# FEV-60_Motor_Driver_Mcu.net
KiCad netlist of a schematic drawn in Altium Designer
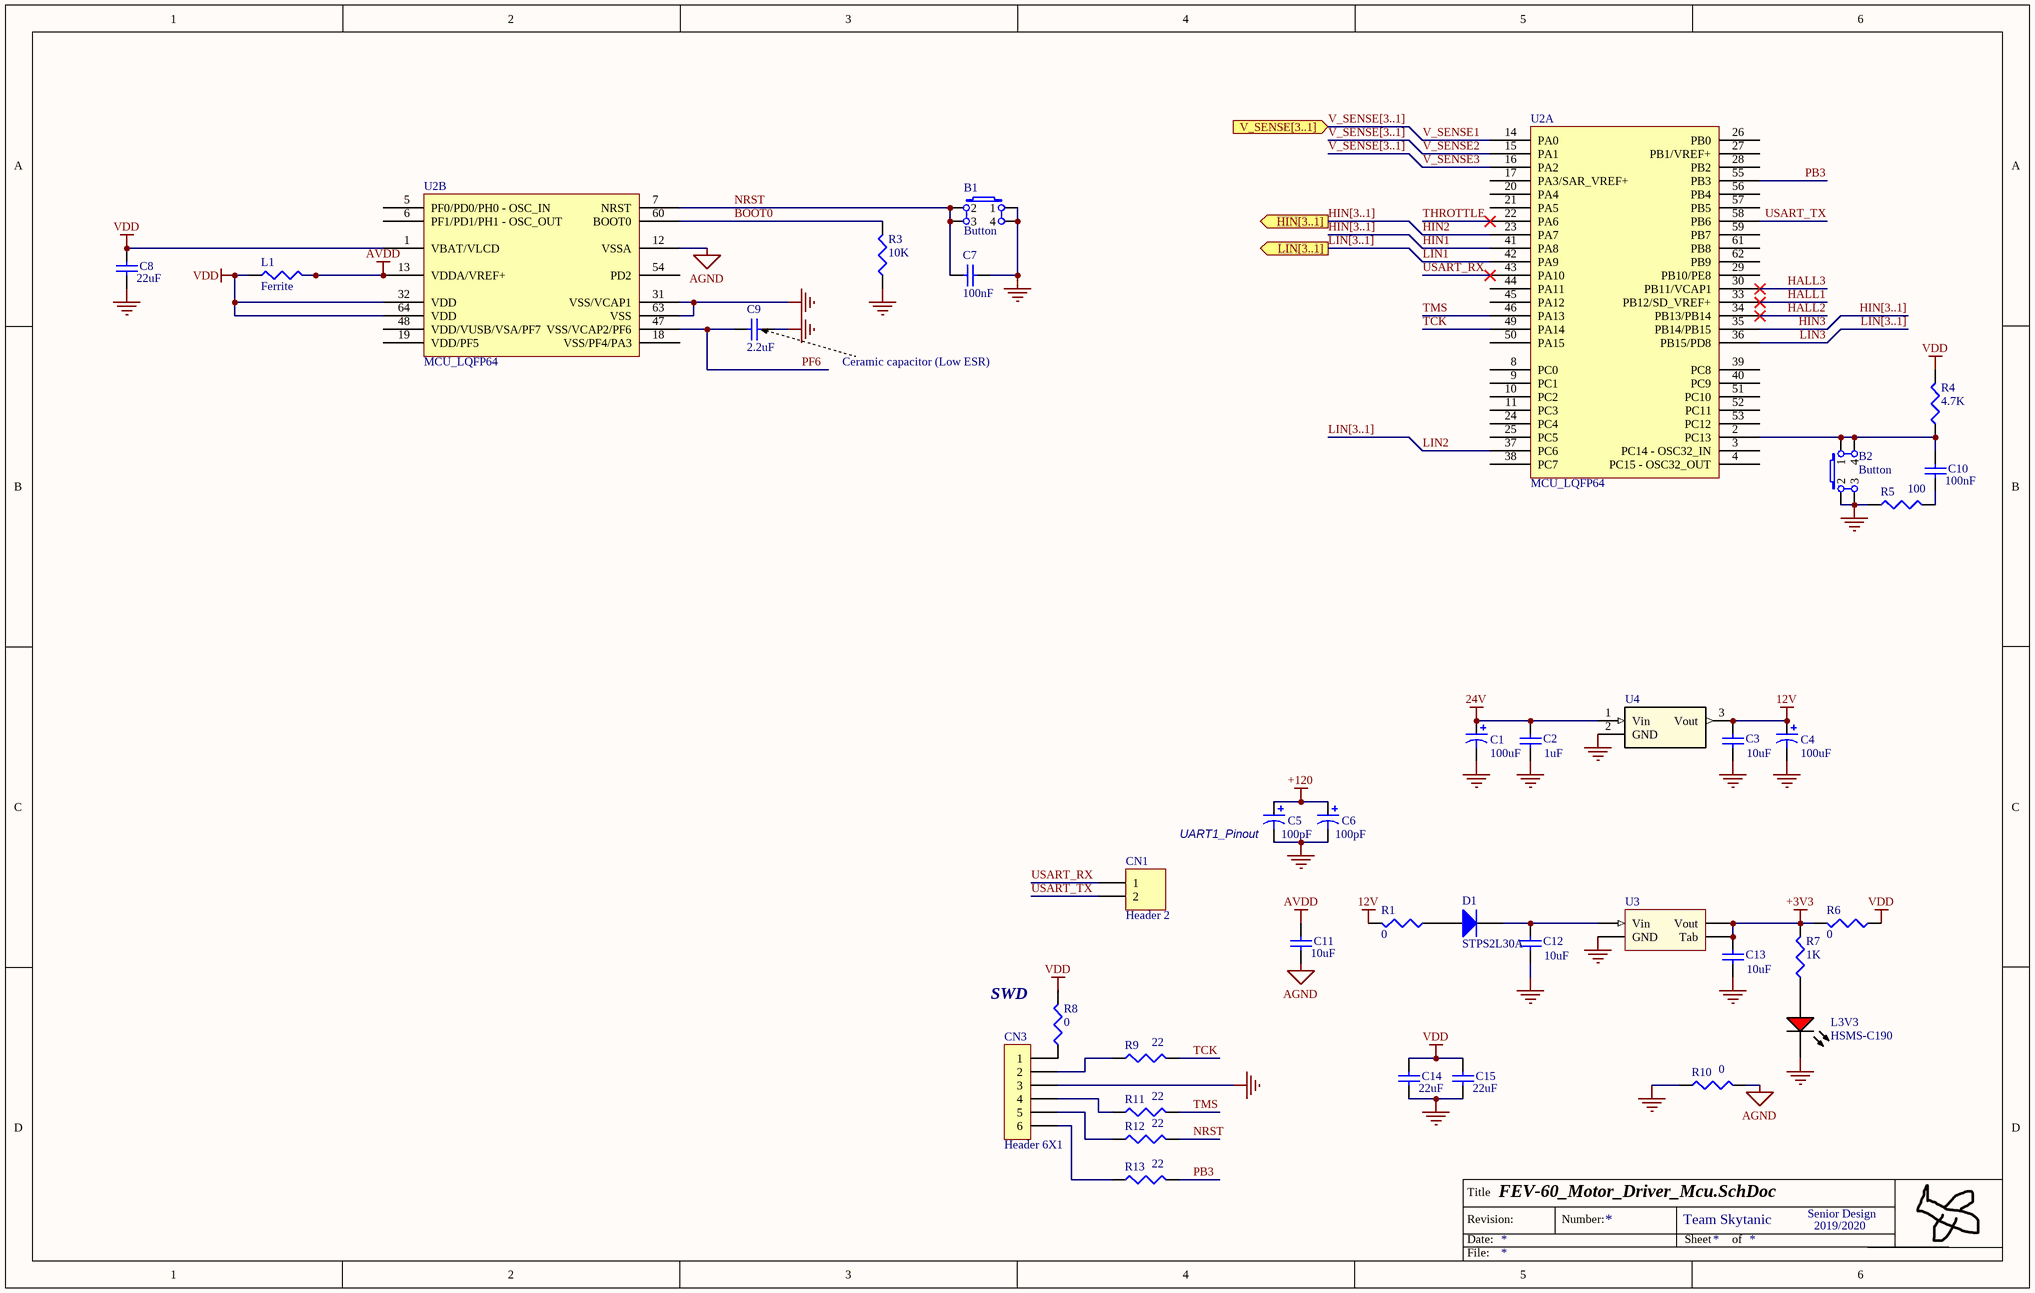
[diagram p0: FEV-60_Motor_Driver_Mcu.SchDoc]

(export (version "E")
  (design (tool "Eeschema 10.0.6"))
  (components
    (comp (ref "B1")
      (value "Button")
      (footprint "Button - duplicate")
      (libsource (lib "FEV-60_Lib") (part "Button"))
    )
    (comp (ref "B2")
      (value "Button")
      (footprint "Button - duplicate")
      (libsource (lib "FEV-60_Lib") (part "Button"))
    )
    (comp (ref "C1")
      (value "100uF")
      (footprint "UVY1V101MED1TD")
      (description "Polarized Capacitor (Axial)")
      (fields (field (name "Comment") "UVY1V101MED1TD") (field (name "PUBLISHER") "Altium Limited"))
      (libsource (lib "FEV-60_Lib") (part "UVY1V101MED1TD"))
    )
    (comp (ref "C2")
      (value "1uF")
      (footprint "1608[0603]")
      (description "Capacitor (Semiconductor SIM Model)")
      (fields (field (name "Comment") "Cap Semi") (field (name "PUBLISHER") "Altium Limited"))
      (libsource (lib "Miscellaneous Devices") (part "Cap Semi"))
    )
    (comp (ref "C3")
      (value "10uF")
      (footprint "1608[0603]")
      (description "Capacitor (Semiconductor SIM Model)")
      (fields (field (name "Comment") "Cap Semi") (field (name "PUBLISHER") "Altium Limited"))
      (libsource (lib "Miscellaneous Devices") (part "Cap Semi"))
    )
    (comp (ref "C4")
      (value "100uF")
      (footprint "UVY1V101MED1TD")
      (description "Polarized Capacitor (Axial)")
      (fields (field (name "Comment") "UVY1V101MED1TD") (field (name "PUBLISHER") "Altium Limited"))
      (libsource (lib "FEV-60_Lib") (part "UVY1V101MED1TD"))
    )
    (comp (ref "C5")
      (value "100pF")
      (footprint "UCS2D151MHD1TN")
      (description "Polarized Capacitor (Axial)")
      (fields (field (name "Comment") "UCS2D151MHD1TN") (field (name "PUBLISHER") "Altium Limited"))
      (libsource (lib "FEV-60_Lib") (part "UCS2D151MHD1TN"))
    )
    (comp (ref "C6")
      (value "100pF")
      (footprint "UCS2D151MHD1TN")
      (description "Polarized Capacitor (Axial)")
      (fields (field (name "Comment") "UCS2D151MHD1TN") (field (name "PUBLISHER") "Altium Limited"))
      (libsource (lib "FEV-60_Lib") (part "UCS2D151MHD1TN"))
    )
    (comp (ref "C7")
      (value "100nF")
      (footprint "1608[0603]")
      (description "Capacitor (Semiconductor SIM Model)")
      (fields (field (name "Comment") "Cap Semi") (field (name "PUBLISHER") "Altium Limited"))
      (libsource (lib "Miscellaneous Devices") (part "Cap Semi"))
    )
    (comp (ref "C8")
      (value "22uF")
      (footprint "1608[0603]")
      (description "Capacitor (Semiconductor SIM Model)")
      (fields (field (name "Comment") "Cap Semi") (field (name "PUBLISHER") "Altium Limited"))
      (libsource (lib "Miscellaneous Devices") (part "Cap Semi"))
    )
    (comp (ref "C9")
      (value "2.2uF")
      (footprint "1608[0603]")
      (description "Capacitor (Semiconductor SIM Model)")
      (fields (field (name "Comment") "Cap Semi") (field (name "PUBLISHER") "Altium Limited"))
      (libsource (lib "Miscellaneous Devices") (part "Cap Semi"))
    )
    (comp (ref "C10")
      (value "100nF")
      (footprint "1608[0603]")
      (description "Capacitor (Semiconductor SIM Model)")
      (fields (field (name "Comment") "Cap Semi") (field (name "PUBLISHER") "Altium Limited"))
      (libsource (lib "Miscellaneous Devices") (part "Cap Semi"))
    )
    (comp (ref "C11")
      (value "10uF")
      (footprint "1608[0603]")
      (description "Capacitor (Semiconductor SIM Model)")
      (fields (field (name "Comment") "Cap Semi") (field (name "PUBLISHER") "Altium Limited"))
      (libsource (lib "Miscellaneous Devices") (part "Cap Semi"))
    )
    (comp (ref "C12")
      (value "10uF")
      (footprint "1608[0603]")
      (description "Capacitor (Semiconductor SIM Model)")
      (fields (field (name "Comment") "Cap Semi") (field (name "PUBLISHER") "Altium Limited"))
      (libsource (lib "Miscellaneous Devices") (part "Cap Semi"))
    )
    (comp (ref "C13")
      (value "10uF")
      (footprint "1608[0603]")
      (description "Capacitor (Semiconductor SIM Model)")
      (fields (field (name "Comment") "Cap Semi") (field (name "PUBLISHER") "Altium Limited"))
      (libsource (lib "Miscellaneous Devices") (part "Cap Semi"))
    )
    (comp (ref "C14")
      (value "22uF")
      (footprint "1608[0603]")
      (description "Capacitor (Semiconductor SIM Model)")
      (fields (field (name "Comment") "Cap Semi") (field (name "PUBLISHER") "Altium Limited"))
      (libsource (lib "Miscellaneous Devices") (part "Cap Semi"))
    )
    (comp (ref "C15")
      (value "22uF")
      (footprint "1608[0603]")
      (description "Capacitor (Semiconductor SIM Model)")
      (fields (field (name "Comment") "Cap Semi") (field (name "PUBLISHER") "Altium Limited"))
      (libsource (lib "Miscellaneous Devices") (part "Cap Semi"))
    )
    (comp (ref "CN1")
      (value "Header 2")
      (footprint "HDR1X2")
      (description "Header, 2-Pin")
      (fields (field (name "PUBLISHER") "Altium Limited"))
      (libsource (lib "Miscellaneous Connectors") (part "Header 2"))
    )
    (comp (ref "CN3")
      (value "Header 6X1")
      (footprint "HDR1X6")
      (description "Header, 6-Pin, Single row")
      (fields (field (name "PUBLISHER") "Altium Limited"))
      (libsource (lib "Nucleo_64") (part "Header 6X1"))
    )
    (comp (ref "D1")
      (value "STPS2L30A")
      (footprint "STPS2L30A")
      (libsource (lib "FEV-60_Lib") (part "STPS2L30A"))
    )
    (comp (ref "L1")
      (value "Ferrite")
      (footprint "J1-0603")
      (description "Resistor")
      (fields (field (name "PUBLISHER") "Altium Limited"))
      (libsource (lib "Miscellaneous Devices") (part "Res3"))
    )
    (comp (ref "L3V3")
      (value "HSMS-C190")
      (footprint "AVAG-HSMX-C190_V")
      (description "LED Uni-Color Red, 52 mW, 20 mA, -40 to 85 degC, 2-Pin SMD, RoHS, Tape and Reel")
      (fields (field (name "MANUFACTURER") "Avago"))
      (libsource (lib "Altium Content Vault") (part "LED-RED-AK-2"))
    )
    (comp (ref "R1")
      (value "0")
      (footprint "J1-0603")
      (description "Resistor")
      (fields (field (name "Comment") "Res3") (field (name "PUBLISHER") "Altium Limited"))
      (libsource (lib "Miscellaneous Devices") (part "Res3"))
    )
    (comp (ref "R3")
      (value "10K")
      (footprint "J1-0603")
      (description "Resistor")
      (fields (field (name "Comment") "Res3") (field (name "PUBLISHER") "Altium Limited"))
      (libsource (lib "Miscellaneous Devices") (part "Res3"))
    )
    (comp (ref "R4")
      (value "4.7K")
      (footprint "J1-0603")
      (description "Resistor")
      (fields (field (name "Comment") "Res3") (field (name "PUBLISHER") "Altium Limited"))
      (libsource (lib "Miscellaneous Devices") (part "Res3"))
    )
    (comp (ref "R5")
      (value "100")
      (footprint "J1-0603")
      (description "Resistor")
      (fields (field (name "Comment") "Res3") (field (name "PUBLISHER") "Altium Limited"))
      (libsource (lib "Miscellaneous Devices") (part "Res3"))
    )
    (comp (ref "R6")
      (value "0")
      (footprint "J1-0603")
      (description "Resistor")
      (fields (field (name "Comment") "Res3") (field (name "PUBLISHER") "Altium Limited"))
      (libsource (lib "Miscellaneous Devices") (part "Res3"))
    )
    (comp (ref "R7")
      (value "1K")
      (footprint "J1-0603")
      (description "Resistor")
      (fields (field (name "Comment") "Res3") (field (name "PUBLISHER") "Altium Limited"))
      (libsource (lib "Miscellaneous Devices") (part "Res3"))
    )
    (comp (ref "R8")
      (value "0")
      (footprint "J1-0603")
      (description "Resistor")
      (fields (field (name "Comment") "Res3") (field (name "PUBLISHER") "Altium Limited"))
      (libsource (lib "Miscellaneous Devices") (part "Res3"))
    )
    (comp (ref "R9")
      (value "22")
      (footprint "J1-0603")
      (description "Resistor")
      (fields (field (name "Comment") "Res3") (field (name "PUBLISHER") "Altium Limited"))
      (libsource (lib "Miscellaneous Devices") (part "Res3"))
    )
    (comp (ref "R10")
      (value "0")
      (footprint "J1-0603")
      (description "Resistor")
      (fields (field (name "Comment") "Res3") (field (name "PUBLISHER") "Altium Limited"))
      (libsource (lib "Miscellaneous Devices") (part "Res3"))
    )
    (comp (ref "R11")
      (value "22")
      (footprint "J1-0603")
      (description "Resistor")
      (fields (field (name "Comment") "Res3") (field (name "PUBLISHER") "Altium Limited"))
      (libsource (lib "Miscellaneous Devices") (part "Res3"))
    )
    (comp (ref "R12")
      (value "22")
      (footprint "J1-0603")
      (description "Resistor")
      (fields (field (name "Comment") "Res3") (field (name "PUBLISHER") "Altium Limited"))
      (libsource (lib "Miscellaneous Devices") (part "Res3"))
    )
    (comp (ref "R13")
      (value "22")
      (footprint "J1-0603")
      (description "Resistor")
      (fields (field (name "Comment") "Res3") (field (name "PUBLISHER") "Altium Limited"))
      (libsource (lib "Miscellaneous Devices") (part "Res3"))
    )
    (comp (ref "U2")
      (value "MCU_LQFP64")
      (footprint "STM32F030R8 - duplicate")
      (libsource (lib "FEV-60_Lib") (part "MCU_LQFP64"))
    )
    (comp (ref "U3")
      (value "LD1117S33TR")
      (footprint "LD1117S33TR - duplicate")
      (libsource (lib "FEV-60_Lib") (part "LD1117S33TR"))
    )
    (comp (ref "U4")
      (value "UA78M12CKVURG3")
      (footprint "UA78M12CKVURG3")
      (description "No Description Available")
      (fields
        (field (name "MANUFACTURER") "Texas Instruments")
        (field (name "COPYRIGHT") "Copyright (C) 2018 Accelerated Designs. All rights reserved")
      )
      (libsource (lib "FEV-60_Lib") (part "UA78M12CKVURG3"))
    )
  )
  (nets
    (net (code "1") (name "+3V3") (class "Default")
      (node (ref "C13") (pin "2") (pinfunction "2_2") (pintype "passive"))
      (node (ref "R6") (pin "2") (pinfunction "2_2") (pintype "passive"))
      (node (ref "R7") (pin "2") (pinfunction "2_2") (pintype "passive"))
      (node (ref "U3") (pin "2") (pinfunction "Vout_2") (pintype "passive"))
      (node (ref "U3") (pin "4") (pinfunction "Tab_4") (pintype "passive"))
    )
    (net (code "2") (name "+120") (class "Default")
      (node (ref "C5") (pin "1") (pinfunction "1_1") (pintype "passive"))
      (node (ref "C6") (pin "1") (pinfunction "1_1") (pintype "passive"))
    )
    (net (code "3") (name "/BOOT0") (class "Default")
      (node (ref "R3") (pin "2") (pinfunction "2_2") (pintype "passive"))
      (node (ref "U2") (pin "60") (pinfunction "BOOT0_60") (pintype "passive"))
    )
    (net (code "4") (name "/HALL1") (class "Default")
      (node (ref "U2") (pin "33") (pinfunction "PB12/SD_VREF+_33") (pintype "passive+no_connect"))
    )
    (net (code "5") (name "/HALL2") (class "Default")
      (node (ref "U2") (pin "34") (pinfunction "PB13/PB14_34") (pintype "passive+no_connect"))
    )
    (net (code "6") (name "/HALL3") (class "Default")
      (node (ref "U2") (pin "30") (pinfunction "PB11/VCAP1_30") (pintype "passive+no_connect"))
    )
    (net (code "7") (name "/HIN1") (class "Default")
      (node (ref "U2") (pin "41") (pinfunction "PA8_41") (pintype "passive"))
    )
    (net (code "8") (name "/HIN2") (class "Default")
      (node (ref "U2") (pin "23") (pinfunction "PA7_23") (pintype "passive"))
    )
    (net (code "9") (name "/HIN3") (class "Default")
      (node (ref "U2") (pin "35") (pinfunction "PB14/PB15_35") (pintype "passive"))
    )
    (net (code "11") (name "/LIN1") (class "Default")
      (node (ref "U2") (pin "42") (pinfunction "PA9_42") (pintype "passive"))
    )
    (net (code "12") (name "/LIN2") (class "Default")
      (node (ref "U2") (pin "37") (pinfunction "PC6_37") (pintype "passive"))
    )
    (net (code "13") (name "/LIN3") (class "Default")
      (node (ref "U2") (pin "36") (pinfunction "PB15/PD8_36") (pintype "passive"))
    )
    (net (code "15") (name "/NRST") (class "Default")
      (node (ref "B1") (pin "2") (pinfunction "2_2") (pintype "passive"))
      (node (ref "B1") (pin "3") (pinfunction "3_3") (pintype "passive"))
      (node (ref "C7") (pin "2") (pinfunction "2_2") (pintype "passive"))
      (node (ref "R12") (pin "2") (pinfunction "2_2") (pintype "passive"))
      (node (ref "U2") (pin "7") (pinfunction "NRST_7") (pintype "passive"))
    )
    (net (code "16") (name "/PB3") (class "Default")
      (node (ref "R13") (pin "2") (pinfunction "2_2") (pintype "passive"))
      (node (ref "U2") (pin "55") (pinfunction "PB3_55") (pintype "passive"))
    )
    (net (code "17") (name "/PF6") (class "Default")
      (node (ref "C9") (pin "2") (pinfunction "2_2") (pintype "passive"))
      (node (ref "U2") (pin "47") (pinfunction "VSS/VCAP2/PF6_47") (pintype "passive"))
    )
    (net (code "18") (name "/TCK") (class "Default")
      (node (ref "R9") (pin "2") (pinfunction "2_2") (pintype "passive"))
      (node (ref "U2") (pin "49") (pinfunction "PA14_49") (pintype "passive"))
    )
    (net (code "19") (name "/THROTTLE") (class "Default")
      (node (ref "U2") (pin "22") (pinfunction "PA6_22") (pintype "passive+no_connect"))
    )
    (net (code "20") (name "/TMS") (class "Default")
      (node (ref "R11") (pin "2") (pinfunction "2_2") (pintype "passive"))
      (node (ref "U2") (pin "46") (pinfunction "PA13_46") (pintype "passive"))
    )
    (net (code "21") (name "/USART_RX") (class "Default")
      (node (ref "CN1") (pin "1") (pinfunction "1_1") (pintype "passive"))
      (node (ref "U2") (pin "43") (pinfunction "PA10_43") (pintype "passive"))
    )
    (net (code "22") (name "/USART_TX") (class "Default")
      (node (ref "CN1") (pin "2") (pinfunction "2_2") (pintype "passive"))
      (node (ref "U2") (pin "58") (pinfunction "PB6_58") (pintype "passive"))
    )
    (net (code "23") (name "/V_SENSE1") (class "Default")
      (node (ref "U2") (pin "14") (pinfunction "PA0_14") (pintype "passive"))
    )
    (net (code "24") (name "/V_SENSE2") (class "Default")
      (node (ref "U2") (pin "15") (pinfunction "PA1_15") (pintype "passive"))
    )
    (net (code "25") (name "/V_SENSE3") (class "Default")
      (node (ref "U2") (pin "16") (pinfunction "PA2_16") (pintype "passive"))
    )
    (net (code "27") (name "12V") (class "Default")
      (node (ref "C3") (pin "2") (pinfunction "2_2") (pintype "passive"))
      (node (ref "C4") (pin "1") (pinfunction "1_1") (pintype "passive"))
      (node (ref "R1") (pin "2") (pinfunction "2_2") (pintype "passive"))
      (node (ref "U4") (pin "3") (pinfunction "Vout_3") (pintype "output"))
    )
    (net (code "28") (name "24V") (class "Default")
      (node (ref "C1") (pin "1") (pinfunction "1_1") (pintype "passive"))
      (node (ref "C2") (pin "2") (pinfunction "2_2") (pintype "passive"))
      (node (ref "U4") (pin "1") (pinfunction "Vin_1") (pintype "input"))
    )
    (net (code "29") (name "AGND") (class "Default")
      (node (ref "C11") (pin "1") (pinfunction "1_1") (pintype "passive"))
      (node (ref "R10") (pin "2") (pinfunction "2_2") (pintype "passive"))
      (node (ref "U2") (pin "12") (pinfunction "VSSA_12") (pintype "passive"))
    )
    (net (code "30") (name "AVDD") (class "Default")
      (node (ref "C11") (pin "2") (pinfunction "2_2") (pintype "passive"))
      (node (ref "L1") (pin "2") (pinfunction "2_2") (pintype "passive"))
      (node (ref "U2") (pin "13") (pinfunction "VDDA/VREF+_13") (pintype "passive"))
    )
    (net (code "31") (name "GND") (class "Default")
      (node (ref "B1") (pin "1") (pinfunction "1_1") (pintype "passive"))
      (node (ref "B1") (pin "4") (pinfunction "4_4") (pintype "passive"))
      (node (ref "B2") (pin "2") (pinfunction "2_2") (pintype "passive"))
      (node (ref "B2") (pin "3") (pinfunction "3_3") (pintype "passive"))
      (node (ref "C1") (pin "2") (pinfunction "2_2") (pintype "passive"))
      (node (ref "C12") (pin "1") (pinfunction "1_1") (pintype "passive"))
      (node (ref "C13") (pin "1") (pinfunction "1_1") (pintype "passive"))
      (node (ref "C14") (pin "1") (pinfunction "1_1") (pintype "passive"))
      (node (ref "C15") (pin "1") (pinfunction "1_1") (pintype "passive"))
      (node (ref "C2") (pin "1") (pinfunction "1_1") (pintype "passive"))
      (node (ref "C3") (pin "1") (pinfunction "1_1") (pintype "passive"))
      (node (ref "C4") (pin "2") (pinfunction "2_2") (pintype "passive"))
      (node (ref "C5") (pin "2") (pinfunction "2_2") (pintype "passive"))
      (node (ref "C6") (pin "2") (pinfunction "2_2") (pintype "passive"))
      (node (ref "C7") (pin "1") (pinfunction "1_1") (pintype "passive"))
      (node (ref "C8") (pin "1") (pinfunction "1_1") (pintype "passive"))
      (node (ref "C9") (pin "1") (pinfunction "1_1") (pintype "passive"))
      (node (ref "CN3") (pin "3") (pinfunction "3_3") (pintype "passive"))
      (node (ref "L3V3") (pin "2") (pinfunction "K_2") (pintype "passive"))
      (node (ref "R10") (pin "1") (pinfunction "1_1") (pintype "passive"))
      (node (ref "R3") (pin "1") (pinfunction "1_1") (pintype "passive"))
      (node (ref "R5") (pin "1") (pinfunction "1_1") (pintype "passive"))
      (node (ref "U2") (pin "31") (pinfunction "VSS/VCAP1_31") (pintype "passive"))
      (node (ref "U2") (pin "63") (pinfunction "VSS_63") (pintype "passive"))
      (node (ref "U3") (pin "1") (pinfunction "GND_1") (pintype "passive"))
      (node (ref "U4") (pin "2") (pinfunction "GND_2") (pintype "power_in"))
    )
    (net (code "32") (name "Net-(C10-Pad1)") (class "Default")
      (node (ref "C10") (pin "1") (pinfunction "1_1") (pintype "passive"))
      (node (ref "R5") (pin "2") (pinfunction "2_2") (pintype "passive"))
    )
    (net (code "33") (name "Net-(CN3-Pad1)") (class "Default")
      (node (ref "CN3") (pin "1") (pinfunction "1_1") (pintype "passive"))
      (node (ref "R8") (pin "1") (pinfunction "1_1") (pintype "passive"))
    )
    (net (code "34") (name "Net-(CN3-Pad2)") (class "Default")
      (node (ref "CN3") (pin "2") (pinfunction "2_2") (pintype "passive"))
      (node (ref "R9") (pin "1") (pinfunction "1_1") (pintype "passive"))
    )
    (net (code "35") (name "Net-(CN3-Pad4)") (class "Default")
      (node (ref "CN3") (pin "4") (pinfunction "4_4") (pintype "passive"))
      (node (ref "R11") (pin "1") (pinfunction "1_1") (pintype "passive"))
    )
    (net (code "36") (name "Net-(CN3-Pad5)") (class "Default")
      (node (ref "CN3") (pin "5") (pinfunction "5_5") (pintype "passive"))
      (node (ref "R12") (pin "1") (pinfunction "1_1") (pintype "passive"))
    )
    (net (code "37") (name "Net-(CN3-Pad6)") (class "Default")
      (node (ref "CN3") (pin "6") (pinfunction "6_6") (pintype "passive"))
      (node (ref "R13") (pin "1") (pinfunction "1_1") (pintype "passive"))
    )
    (net (code "38") (name "Net-(D1-A)") (class "Default")
      (node (ref "D1") (pin "1") (pinfunction "A_1") (pintype "passive"))
      (node (ref "R1") (pin "1") (pinfunction "1_1") (pintype "passive"))
    )
    (net (code "39") (name "Net-(D1-K)") (class "Default")
      (node (ref "C12") (pin "2") (pinfunction "2_2") (pintype "passive"))
      (node (ref "D1") (pin "2") (pinfunction "K_2") (pintype "passive"))
      (node (ref "U3") (pin "3") (pinfunction "Vin_3") (pintype "input"))
    )
    (net (code "40") (name "Net-(L3V3-A)") (class "Default")
      (node (ref "L3V3") (pin "1") (pinfunction "A_1") (pintype "passive"))
      (node (ref "R7") (pin "1") (pinfunction "1_1") (pintype "passive"))
    )
    (net (code "41") (name "Net-(U2A-PC13)") (class "Default")
      (node (ref "B2") (pin "1") (pinfunction "1_1") (pintype "passive"))
      (node (ref "B2") (pin "4") (pinfunction "4_4") (pintype "passive"))
      (node (ref "C10") (pin "2") (pinfunction "2_2") (pintype "passive"))
      (node (ref "R4") (pin "1") (pinfunction "1_1") (pintype "passive"))
      (node (ref "U2") (pin "2") (pinfunction "PC13_2") (pintype "passive"))
    )
    (net (code "42") (name "VDD") (class "Default")
      (node (ref "C14") (pin "2") (pinfunction "2_2") (pintype "passive"))
      (node (ref "C15") (pin "2") (pinfunction "2_2") (pintype "passive"))
      (node (ref "C8") (pin "2") (pinfunction "2_2") (pintype "passive"))
      (node (ref "L1") (pin "1") (pinfunction "1_1") (pintype "passive"))
      (node (ref "R4") (pin "2") (pinfunction "2_2") (pintype "passive"))
      (node (ref "R6") (pin "1") (pinfunction "1_1") (pintype "passive"))
      (node (ref "R8") (pin "2") (pinfunction "2_2") (pintype "passive"))
      (node (ref "U2") (pin "1") (pinfunction "VBAT/VLCD_1") (pintype "passive"))
      (node (ref "U2") (pin "32") (pinfunction "VDD_32") (pintype "passive"))
      (node (ref "U2") (pin "64") (pinfunction "VDD_64") (pintype "passive"))
    )
    (net (code "43") (name "unconnected-(U2A-PA3{slash}SAR_VREF+-Pad17)") (class "Default")
      (node (ref "U2") (pin "17") (pinfunction "PA3/SAR_VREF+_17") (pintype "passive"))
    )
    (net (code "44") (name "unconnected-(U2A-PA4-Pad20)") (class "Default")
      (node (ref "U2") (pin "20") (pinfunction "PA4_20") (pintype "passive"))
    )
    (net (code "45") (name "unconnected-(U2A-PA5-Pad21)") (class "Default")
      (node (ref "U2") (pin "21") (pinfunction "PA5_21") (pintype "passive"))
    )
    (net (code "46") (name "unconnected-(U2A-PA11-Pad44)") (class "Default")
      (node (ref "U2") (pin "44") (pinfunction "PA11_44") (pintype "passive"))
    )
    (net (code "47") (name "unconnected-(U2A-PA12-Pad45)") (class "Default")
      (node (ref "U2") (pin "45") (pinfunction "PA12_45") (pintype "passive"))
    )
    (net (code "48") (name "unconnected-(U2A-PA15-Pad50)") (class "Default")
      (node (ref "U2") (pin "50") (pinfunction "PA15_50") (pintype "passive"))
    )
    (net (code "49") (name "unconnected-(U2A-PB0-Pad26)") (class "Default")
      (node (ref "U2") (pin "26") (pinfunction "PB0_26") (pintype "passive"))
    )
    (net (code "50") (name "unconnected-(U2A-PB1{slash}VREF+-Pad27)") (class "Default")
      (node (ref "U2") (pin "27") (pinfunction "PB1/VREF+_27") (pintype "passive"))
    )
    (net (code "51") (name "unconnected-(U2A-PB2-Pad28)") (class "Default")
      (node (ref "U2") (pin "28") (pinfunction "PB2_28") (pintype "passive"))
    )
    (net (code "52") (name "unconnected-(U2A-PB4-Pad56)") (class "Default")
      (node (ref "U2") (pin "56") (pinfunction "PB4_56") (pintype "passive"))
    )
    (net (code "53") (name "unconnected-(U2A-PB5-Pad57)") (class "Default")
      (node (ref "U2") (pin "57") (pinfunction "PB5_57") (pintype "passive"))
    )
    (net (code "54") (name "unconnected-(U2A-PB7-Pad59)") (class "Default")
      (node (ref "U2") (pin "59") (pinfunction "PB7_59") (pintype "passive"))
    )
    (net (code "55") (name "unconnected-(U2A-PB8-Pad61)") (class "Default")
      (node (ref "U2") (pin "61") (pinfunction "PB8_61") (pintype "passive"))
    )
    (net (code "56") (name "unconnected-(U2A-PB9-Pad62)") (class "Default")
      (node (ref "U2") (pin "62") (pinfunction "PB9_62") (pintype "passive"))
    )
    (net (code "57") (name "unconnected-(U2A-PB10{slash}PE8-Pad29)") (class "Default")
      (node (ref "U2") (pin "29") (pinfunction "PB10/PE8_29") (pintype "passive"))
    )
    (net (code "58") (name "unconnected-(U2A-PC0-Pad8)") (class "Default")
      (node (ref "U2") (pin "8") (pinfunction "PC0_8") (pintype "passive"))
    )
    (net (code "59") (name "unconnected-(U2A-PC1-Pad9)") (class "Default")
      (node (ref "U2") (pin "9") (pinfunction "PC1_9") (pintype "passive"))
    )
    (net (code "60") (name "unconnected-(U2A-PC2-Pad10)") (class "Default")
      (node (ref "U2") (pin "10") (pinfunction "PC2_10") (pintype "passive"))
    )
    (net (code "61") (name "unconnected-(U2A-PC3-Pad11)") (class "Default")
      (node (ref "U2") (pin "11") (pinfunction "PC3_11") (pintype "passive"))
    )
    (net (code "62") (name "unconnected-(U2A-PC4-Pad24)") (class "Default")
      (node (ref "U2") (pin "24") (pinfunction "PC4_24") (pintype "passive"))
    )
    (net (code "63") (name "unconnected-(U2A-PC5-Pad25)") (class "Default")
      (node (ref "U2") (pin "25") (pinfunction "PC5_25") (pintype "passive"))
    )
    (net (code "64") (name "unconnected-(U2A-PC7-Pad38)") (class "Default")
      (node (ref "U2") (pin "38") (pinfunction "PC7_38") (pintype "passive"))
    )
    (net (code "65") (name "unconnected-(U2A-PC8-Pad39)") (class "Default")
      (node (ref "U2") (pin "39") (pinfunction "PC8_39") (pintype "passive"))
    )
    (net (code "66") (name "unconnected-(U2A-PC9-Pad40)") (class "Default")
      (node (ref "U2") (pin "40") (pinfunction "PC9_40") (pintype "passive"))
    )
    (net (code "67") (name "unconnected-(U2A-PC10-Pad51)") (class "Default")
      (node (ref "U2") (pin "51") (pinfunction "PC10_51") (pintype "passive"))
    )
    (net (code "68") (name "unconnected-(U2A-PC11-Pad52)") (class "Default")
      (node (ref "U2") (pin "52") (pinfunction "PC11_52") (pintype "passive"))
    )
    (net (code "69") (name "unconnected-(U2A-PC12-Pad53)") (class "Default")
      (node (ref "U2") (pin "53") (pinfunction "PC12_53") (pintype "passive"))
    )
    (net (code "70") (name "unconnected-(U2A-PC14_-_OSC32_IN-Pad3)") (class "Default")
      (node (ref "U2") (pin "3") (pinfunction "PC14_-_OSC32_IN_3") (pintype "passive"))
    )
    (net (code "71") (name "unconnected-(U2A-PC15_-_OSC32_OUT-Pad4)") (class "Default")
      (node (ref "U2") (pin "4") (pinfunction "PC15_-_OSC32_OUT_4") (pintype "passive"))
    )
    (net (code "72") (name "unconnected-(U2B-PD2-Pad54)") (class "Default")
      (node (ref "U2") (pin "54") (pinfunction "PD2_54") (pintype "passive"))
    )
    (net (code "73") (name "unconnected-(U2B-PF0{slash}PD0{slash}PH0_-_OSC_IN-Pad5)") (class "Default")
      (node (ref "U2") (pin "5") (pinfunction "PF0/PD0/PH0_-_OSC_IN_5") (pintype "passive"))
    )
    (net (code "74") (name "unconnected-(U2B-PF1{slash}PD1{slash}PH1_-_OSC_OUT-Pad6)") (class "Default")
      (node (ref "U2") (pin "6") (pinfunction "PF1/PD1/PH1_-_OSC_OUT_6") (pintype "passive"))
    )
    (net (code "75") (name "unconnected-(U2B-VDD{slash}PF5-Pad19)") (class "Default")
      (node (ref "U2") (pin "19") (pinfunction "VDD/PF5_19") (pintype "passive"))
    )
    (net (code "76") (name "unconnected-(U2B-VDD{slash}VUSB{slash}VSA{slash}PF7-Pad48)") (class "Default")
      (node (ref "U2") (pin "48") (pinfunction "VDD/VUSB/VSA/PF7_48") (pintype "passive"))
    )
    (net (code "77") (name "unconnected-(U2B-VSS{slash}PF4{slash}PA3-Pad18)") (class "Default")
      (node (ref "U2") (pin "18") (pinfunction "VSS/PF4/PA3_18") (pintype "passive"))
    )
  )
)
